# SOC_DDR.net
KiCad netlist of a schematic drawn in Altium Designer
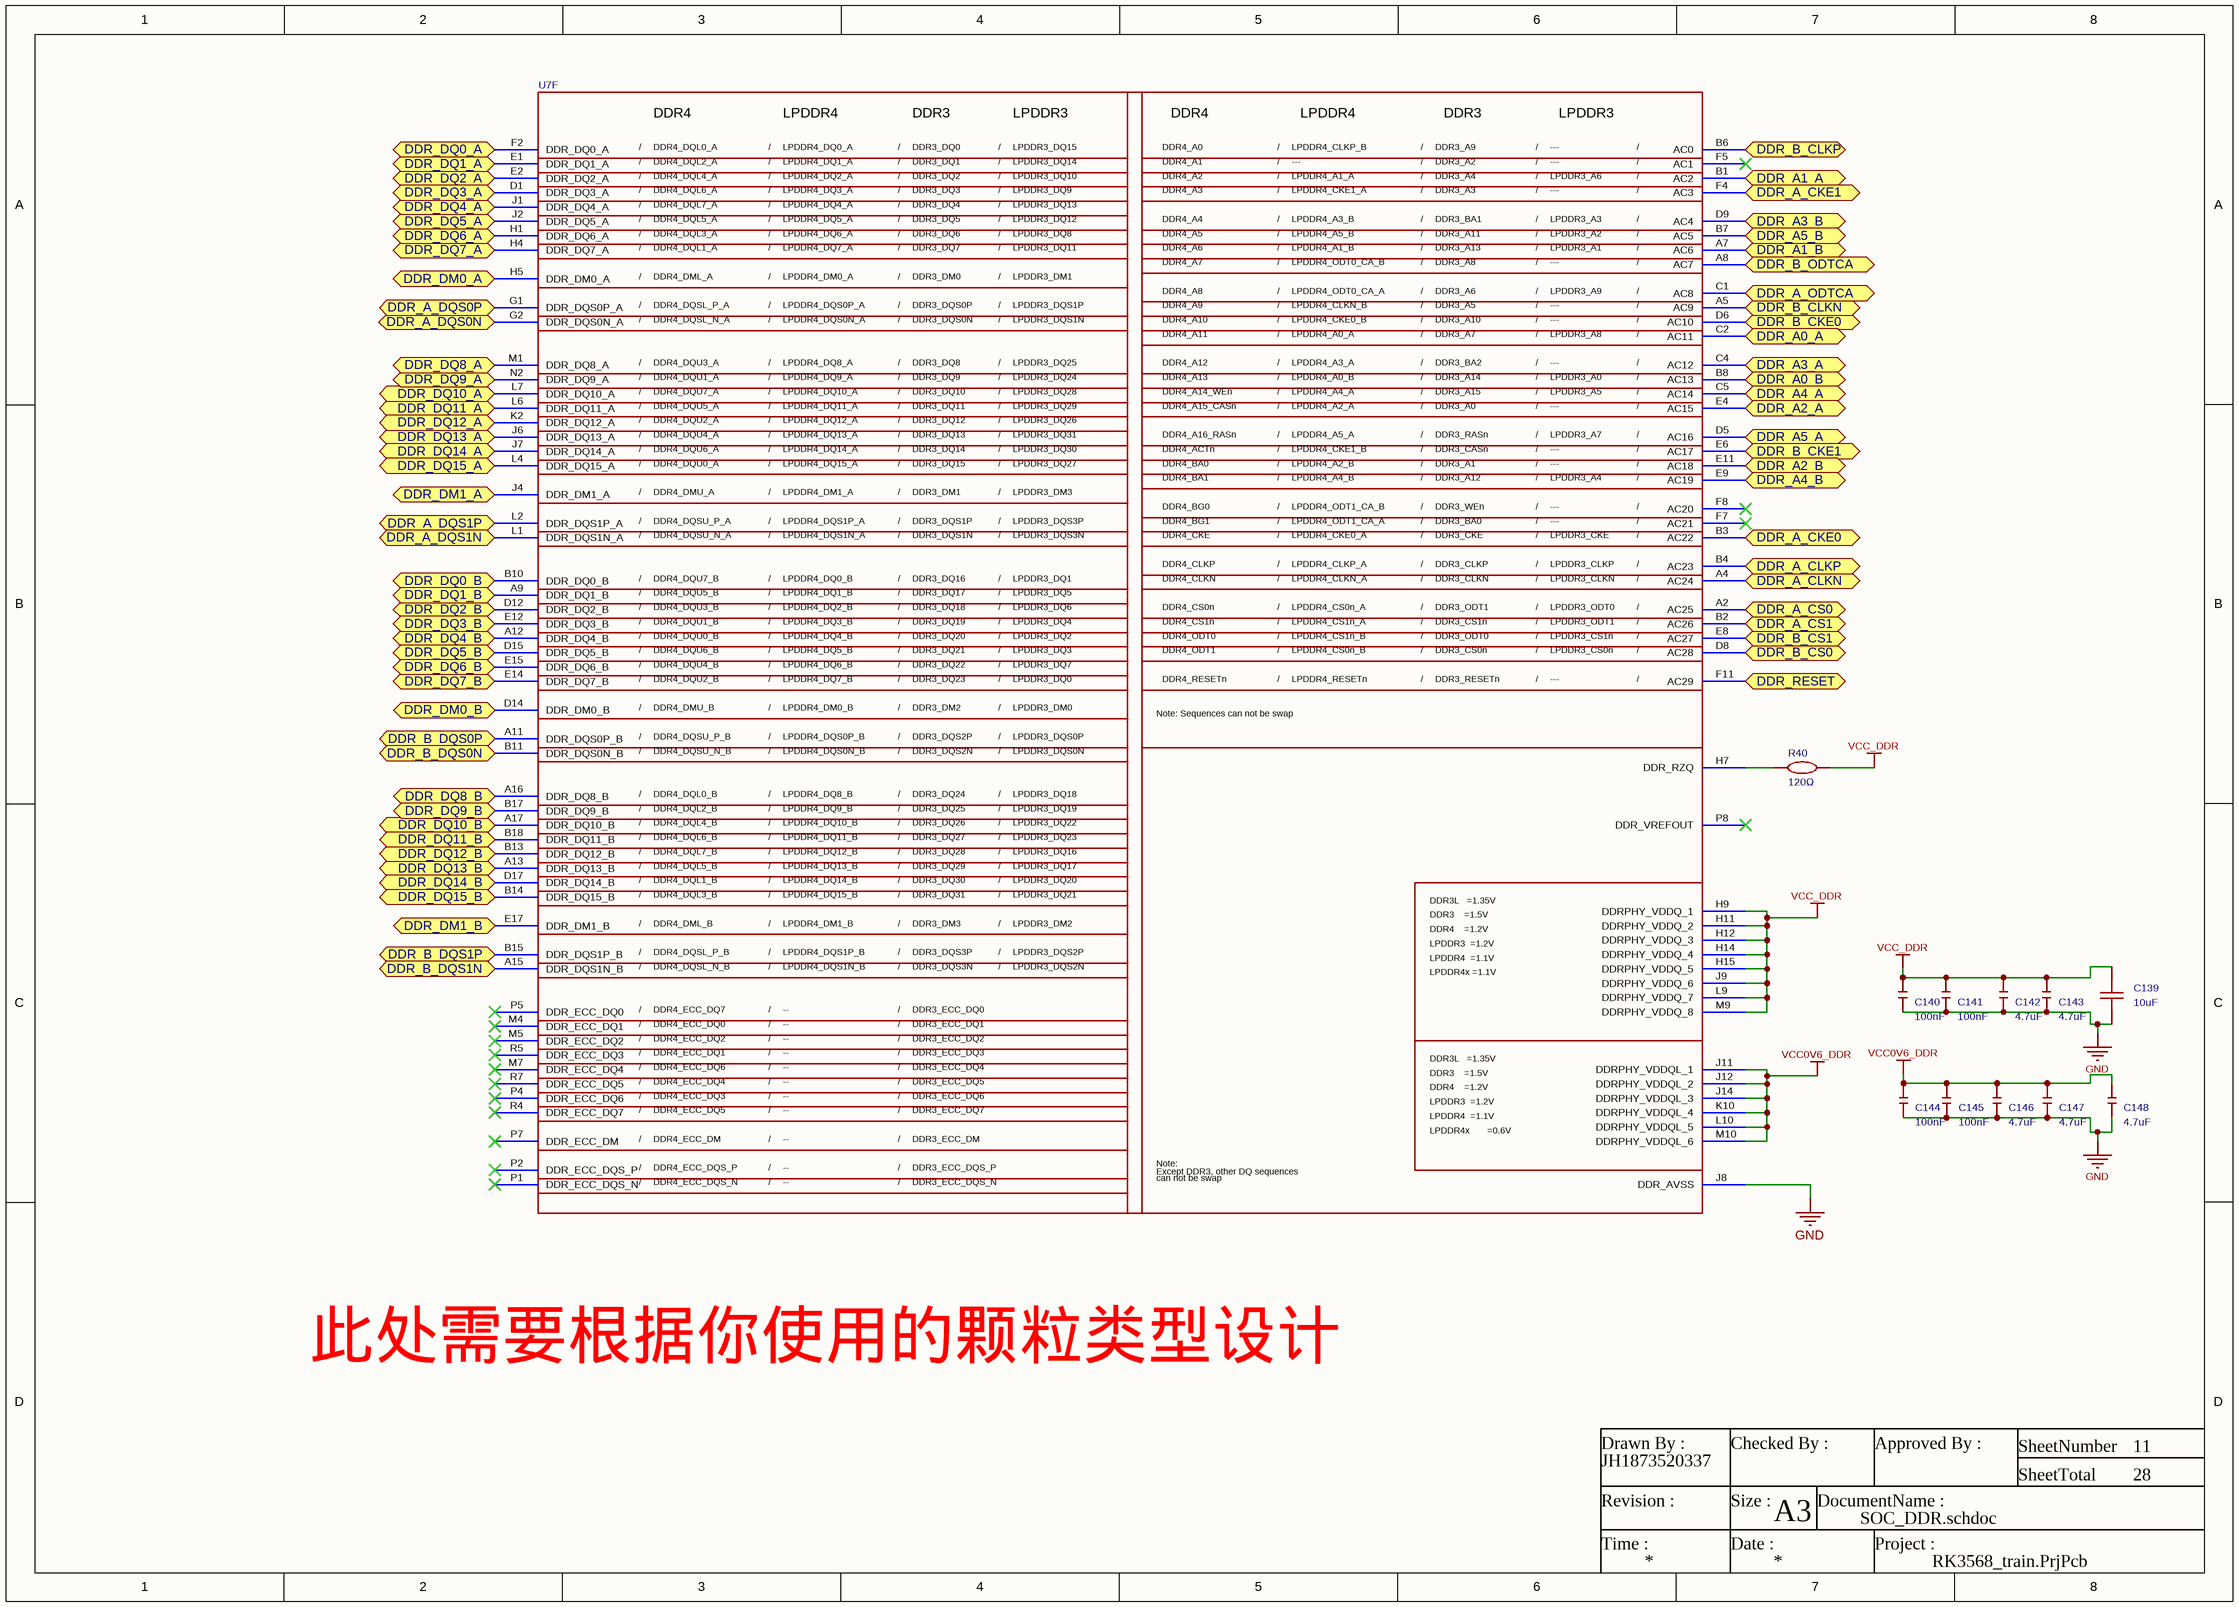
[diagram p0: SOC_DDR.schdoc]

(export (version "E")
  (design (tool "Eeschema 10.0.6"))
  (components
    (comp (ref "C139")
      (value "10uF")
      (footprint "C0603")
      (libsource (lib "altium-import") (part "root_1_CAP_0603_"))
    )
    (comp (ref "C140")
      (value "100nF")
      (footprint "MYC0201")
      (description "my0201")
      (libsource (lib "altium-import") (part "root_1_MY_C0201_"))
    )
    (comp (ref "C141")
      (value "100nF")
      (footprint "MYC0201")
      (description "my0201")
      (libsource (lib "altium-import") (part "root_1_MY_C0201_"))
    )
    (comp (ref "C142")
      (value "4.7uF")
      (footprint "MYC0402")
      (description "C0402电容")
      (libsource (lib "altium-import") (part "root_1_MYC0402_"))
    )
    (comp (ref "C143")
      (value "4.7uF")
      (footprint "MYC0402")
      (description "C0402电容")
      (libsource (lib "altium-import") (part "root_1_MYC0402_"))
    )
    (comp (ref "C144")
      (value "100nF")
      (footprint "MYC0201")
      (description "my0201")
      (libsource (lib "altium-import") (part "root_1_MY_C0201_"))
    )
    (comp (ref "C145")
      (value "100nF")
      (footprint "MYC0201")
      (description "my0201")
      (libsource (lib "altium-import") (part "root_1_MY_C0201_"))
    )
    (comp (ref "C146")
      (value "4.7uF")
      (footprint "MYC0402")
      (description "C0402电容")
      (libsource (lib "altium-import") (part "root_1_MYC0402_"))
    )
    (comp (ref "C147")
      (value "4.7uF")
      (footprint "MYC0402")
      (description "C0402电容")
      (libsource (lib "altium-import") (part "root_1_MYC0402_"))
    )
    (comp (ref "C148")
      (value "4.7uF")
      (footprint "MYC0402")
      (description "C0402电容")
      (libsource (lib "altium-import") (part "root_1_MYC0402_"))
    )
    (comp (ref "R40")
      (value "120Ω")
      (footprint "R0201")
      (libsource (lib "altium-import") (part "root_0_Res_0201_"))
    )
    (comp (ref "U7")
      (value "RK3568")
      (footprint "BGA-636_L19.0-W19.0-P0.65-BL")
      (libsource (lib "altium-import") (part "root_0_RK3568_"))
    )
  )
  (nets
    (net (code "1") (name "/DDR_A0_A") (class "Default")
      (node (ref "U7") (pin "C2") (pinfunction "AC11_C2") (pintype "passive"))
    )
    (net (code "2") (name "/DDR_A0_B") (class "Default")
      (node (ref "U7") (pin "B8") (pinfunction "AC13_B8") (pintype "passive"))
    )
    (net (code "3") (name "/DDR_A1_A") (class "Default")
      (node (ref "U7") (pin "B1") (pinfunction "AC2_B1") (pintype "passive"))
    )
    (net (code "4") (name "/DDR_A1_B") (class "Default")
      (node (ref "U7") (pin "A7") (pinfunction "AC6_A7") (pintype "passive"))
    )
    (net (code "5") (name "/DDR_A2_A") (class "Default")
      (node (ref "U7") (pin "E4") (pinfunction "AC15_E4") (pintype "passive"))
    )
    (net (code "6") (name "/DDR_A2_B") (class "Default")
      (node (ref "U7") (pin "E11") (pinfunction "AC18_E11") (pintype "passive"))
    )
    (net (code "7") (name "/DDR_A3_A") (class "Default")
      (node (ref "U7") (pin "C4") (pinfunction "AC12_C4") (pintype "passive"))
    )
    (net (code "8") (name "/DDR_A3_B") (class "Default")
      (node (ref "U7") (pin "D9") (pinfunction "AC4_D9") (pintype "passive"))
    )
    (net (code "9") (name "/DDR_A4_A") (class "Default")
      (node (ref "U7") (pin "C5") (pinfunction "AC14_C5") (pintype "passive"))
    )
    (net (code "10") (name "/DDR_A4_B") (class "Default")
      (node (ref "U7") (pin "E9") (pinfunction "AC19_E9") (pintype "passive"))
    )
    (net (code "11") (name "/DDR_A5_A") (class "Default")
      (node (ref "U7") (pin "D5") (pinfunction "AC16_D5") (pintype "passive"))
    )
    (net (code "12") (name "/DDR_A5_B") (class "Default")
      (node (ref "U7") (pin "B7") (pinfunction "AC5_B7") (pintype "passive"))
    )
    (net (code "13") (name "/DDR_A_CKE0") (class "Default")
      (node (ref "U7") (pin "B3") (pinfunction "AC22_B3") (pintype "passive"))
    )
    (net (code "14") (name "/DDR_A_CKE1") (class "Default")
      (node (ref "U7") (pin "F4") (pinfunction "AC3_F4") (pintype "passive"))
    )
    (net (code "15") (name "/DDR_A_CLKN") (class "Default")
      (node (ref "U7") (pin "A4") (pinfunction "AC24_A4") (pintype "passive"))
    )
    (net (code "16") (name "/DDR_A_CLKP") (class "Default")
      (node (ref "U7") (pin "B4") (pinfunction "AC23_B4") (pintype "passive"))
    )
    (net (code "17") (name "/DDR_A_CS0") (class "Default")
      (node (ref "U7") (pin "A2") (pinfunction "AC25_A2") (pintype "passive"))
    )
    (net (code "18") (name "/DDR_A_CS1") (class "Default")
      (node (ref "U7") (pin "B2") (pinfunction "AC26_B2") (pintype "passive"))
    )
    (net (code "19") (name "/DDR_A_DQS0N") (class "Default")
      (node (ref "U7") (pin "G2") (pinfunction "DDR_DQS0N_A_G2") (pintype "passive"))
    )
    (net (code "20") (name "/DDR_A_DQS0P") (class "Default")
      (node (ref "U7") (pin "G1") (pinfunction "DDR_DQS0P_A_G1") (pintype "passive"))
    )
    (net (code "21") (name "/DDR_A_DQS1N") (class "Default")
      (node (ref "U7") (pin "L1") (pinfunction "DDR_DQS1N_A_L1") (pintype "passive"))
    )
    (net (code "22") (name "/DDR_A_DQS1P") (class "Default")
      (node (ref "U7") (pin "L2") (pinfunction "DDR_DQS1P_A_L2") (pintype "passive"))
    )
    (net (code "23") (name "/DDR_A_ODTCA") (class "Default")
      (node (ref "U7") (pin "C1") (pinfunction "AC8_C1") (pintype "passive"))
    )
    (net (code "24") (name "/DDR_B_CKE0") (class "Default")
      (node (ref "U7") (pin "D6") (pinfunction "AC10_D6") (pintype "passive"))
    )
    (net (code "25") (name "/DDR_B_CKE1") (class "Default")
      (node (ref "U7") (pin "E6") (pinfunction "AC17_E6") (pintype "passive"))
    )
    (net (code "26") (name "/DDR_B_CLKN") (class "Default")
      (node (ref "U7") (pin "A5") (pinfunction "AC9_A5") (pintype "passive"))
    )
    (net (code "27") (name "/DDR_B_CLKP") (class "Default")
      (node (ref "U7") (pin "B6") (pinfunction "AC0_B6") (pintype "passive"))
    )
    (net (code "28") (name "/DDR_B_CS0") (class "Default")
      (node (ref "U7") (pin "D8") (pinfunction "AC28_D8") (pintype "passive"))
    )
    (net (code "29") (name "/DDR_B_CS1") (class "Default")
      (node (ref "U7") (pin "E8") (pinfunction "AC27_E8") (pintype "passive"))
    )
    (net (code "30") (name "/DDR_B_DQS0N") (class "Default")
      (node (ref "U7") (pin "B11") (pinfunction "DDR_DQS0N_B_B11") (pintype "passive"))
    )
    (net (code "31") (name "/DDR_B_DQS0P") (class "Default")
      (node (ref "U7") (pin "A11") (pinfunction "DDR_DQS0P_B_A11") (pintype "passive"))
    )
    (net (code "32") (name "/DDR_B_DQS1N") (class "Default")
      (node (ref "U7") (pin "A15") (pinfunction "DDR_DQS1N_B_A15") (pintype "passive"))
    )
    (net (code "33") (name "/DDR_B_DQS1P") (class "Default")
      (node (ref "U7") (pin "B15") (pinfunction "DDR_DQS1P_B_B15") (pintype "passive"))
    )
    (net (code "34") (name "/DDR_B_ODTCA") (class "Default")
      (node (ref "U7") (pin "A8") (pinfunction "AC7_A8") (pintype "passive"))
    )
    (net (code "35") (name "/DDR_DM0_A") (class "Default")
      (node (ref "U7") (pin "H5") (pinfunction "DDR_DM0_A_H5") (pintype "passive"))
    )
    (net (code "36") (name "/DDR_DM0_B") (class "Default")
      (node (ref "U7") (pin "D14") (pinfunction "DDR_DM0_B_D14") (pintype "passive"))
    )
    (net (code "37") (name "/DDR_DM1_A") (class "Default")
      (node (ref "U7") (pin "J4") (pinfunction "DDR_DM1_A_J4") (pintype "passive"))
    )
    (net (code "38") (name "/DDR_DM1_B") (class "Default")
      (node (ref "U7") (pin "E17") (pinfunction "DDR_DM1_B_E17") (pintype "passive"))
    )
    (net (code "39") (name "/DDR_DQ0_A") (class "Default")
      (node (ref "U7") (pin "F2") (pinfunction "DDR_DQ0_A_F2") (pintype "passive"))
    )
    (net (code "40") (name "/DDR_DQ0_B") (class "Default")
      (node (ref "U7") (pin "B10") (pinfunction "DDR_DQ0_B_B10") (pintype "passive"))
    )
    (net (code "41") (name "/DDR_DQ1_A") (class "Default")
      (node (ref "U7") (pin "E1") (pinfunction "DDR_DQ1_A_E1") (pintype "passive"))
    )
    (net (code "42") (name "/DDR_DQ1_B") (class "Default")
      (node (ref "U7") (pin "A9") (pinfunction "DDR_DQ1_B_A9") (pintype "passive"))
    )
    (net (code "43") (name "/DDR_DQ2_A") (class "Default")
      (node (ref "U7") (pin "E2") (pinfunction "DDR_DQ2_A_E2") (pintype "passive"))
    )
    (net (code "44") (name "/DDR_DQ2_B") (class "Default")
      (node (ref "U7") (pin "D12") (pinfunction "DDR_DQ2_B_D12") (pintype "passive"))
    )
    (net (code "45") (name "/DDR_DQ3_A") (class "Default")
      (node (ref "U7") (pin "D1") (pinfunction "DDR_DQ3_A_D1") (pintype "passive"))
    )
    (net (code "46") (name "/DDR_DQ3_B") (class "Default")
      (node (ref "U7") (pin "E12") (pinfunction "DDR_DQ3_B_E12") (pintype "passive"))
    )
    (net (code "47") (name "/DDR_DQ4_A") (class "Default")
      (node (ref "U7") (pin "J1") (pinfunction "DDR_DQ4_A_J1") (pintype "passive"))
    )
    (net (code "48") (name "/DDR_DQ4_B") (class "Default")
      (node (ref "U7") (pin "A12") (pinfunction "DDR_DQ4_B_A12") (pintype "passive"))
    )
    (net (code "49") (name "/DDR_DQ5_A") (class "Default")
      (node (ref "U7") (pin "J2") (pinfunction "DDR_DQ5_A_J2") (pintype "passive"))
    )
    (net (code "50") (name "/DDR_DQ5_B") (class "Default")
      (node (ref "U7") (pin "D15") (pinfunction "DDR_DQ5_B_D15") (pintype "passive"))
    )
    (net (code "51") (name "/DDR_DQ6_A") (class "Default")
      (node (ref "U7") (pin "H1") (pinfunction "DDR_DQ6_A_H1") (pintype "passive"))
    )
    (net (code "52") (name "/DDR_DQ6_B") (class "Default")
      (node (ref "U7") (pin "E15") (pinfunction "DDR_DQ6_B_E15") (pintype "passive"))
    )
    (net (code "53") (name "/DDR_DQ7_A") (class "Default")
      (node (ref "U7") (pin "H4") (pinfunction "DDR_DQ7_A_H4") (pintype "passive"))
    )
    (net (code "54") (name "/DDR_DQ7_B") (class "Default")
      (node (ref "U7") (pin "E14") (pinfunction "DDR_DQ7_B_E14") (pintype "passive"))
    )
    (net (code "55") (name "/DDR_DQ8_A") (class "Default")
      (node (ref "U7") (pin "M1") (pinfunction "DDR_DQ8_A_M1") (pintype "passive"))
    )
    (net (code "56") (name "/DDR_DQ8_B") (class "Default")
      (node (ref "U7") (pin "A16") (pinfunction "DDR_DQ8_B_A16") (pintype "passive"))
    )
    (net (code "57") (name "/DDR_DQ9_A") (class "Default")
      (node (ref "U7") (pin "N2") (pinfunction "DDR_DQ9_A_N2") (pintype "passive"))
    )
    (net (code "58") (name "/DDR_DQ9_B") (class "Default")
      (node (ref "U7") (pin "B17") (pinfunction "DDR_DQ9_B_B17") (pintype "passive"))
    )
    (net (code "59") (name "/DDR_DQ10_A") (class "Default")
      (node (ref "U7") (pin "L7") (pinfunction "DDR_DQ10_A_L7") (pintype "passive"))
    )
    (net (code "60") (name "/DDR_DQ10_B") (class "Default")
      (node (ref "U7") (pin "A17") (pinfunction "DDR_DQ10_B_A17") (pintype "passive"))
    )
    (net (code "61") (name "/DDR_DQ11_A") (class "Default")
      (node (ref "U7") (pin "L6") (pinfunction "DDR_DQ11_A_L6") (pintype "passive"))
    )
    (net (code "62") (name "/DDR_DQ11_B") (class "Default")
      (node (ref "U7") (pin "B18") (pinfunction "DDR_DQ11_B_B18") (pintype "passive"))
    )
    (net (code "63") (name "/DDR_DQ12_A") (class "Default")
      (node (ref "U7") (pin "K2") (pinfunction "DDR_DQ12_A_K2") (pintype "passive"))
    )
    (net (code "64") (name "/DDR_DQ12_B") (class "Default")
      (node (ref "U7") (pin "B13") (pinfunction "DDR_DQ12_B_B13") (pintype "passive"))
    )
    (net (code "65") (name "/DDR_DQ13_A") (class "Default")
      (node (ref "U7") (pin "J6") (pinfunction "DDR_DQ13_A_J6") (pintype "passive"))
    )
    (net (code "66") (name "/DDR_DQ13_B") (class "Default")
      (node (ref "U7") (pin "A13") (pinfunction "DDR_DQ13_B_A13") (pintype "passive"))
    )
    (net (code "67") (name "/DDR_DQ14_A") (class "Default")
      (node (ref "U7") (pin "J7") (pinfunction "DDR_DQ14_A_J7") (pintype "passive"))
    )
    (net (code "68") (name "/DDR_DQ14_B") (class "Default")
      (node (ref "U7") (pin "D17") (pinfunction "DDR_DQ14_B_D17") (pintype "passive"))
    )
    (net (code "69") (name "/DDR_DQ15_A") (class "Default")
      (node (ref "U7") (pin "L4") (pinfunction "DDR_DQ15_A_L4") (pintype "passive"))
    )
    (net (code "70") (name "/DDR_DQ15_B") (class "Default")
      (node (ref "U7") (pin "B14") (pinfunction "DDR_DQ15_B_B14") (pintype "passive"))
    )
    (net (code "71") (name "/DDR_RESET") (class "Default")
      (node (ref "U7") (pin "F11") (pinfunction "AC29_F11") (pintype "passive"))
    )
    (net (code "72") (name "GND") (class "Default")
      (node (ref "C139") (pin "1") (pinfunction "1_1") (pintype "passive"))
      (node (ref "C140") (pin "1") (pinfunction "1_1") (pintype "passive"))
      (node (ref "C141") (pin "1") (pinfunction "1_1") (pintype "passive"))
      (node (ref "C142") (pin "1") (pinfunction "1_1") (pintype "passive"))
      (node (ref "C143") (pin "1") (pinfunction "1_1") (pintype "passive"))
      (node (ref "C144") (pin "1") (pinfunction "1_1") (pintype "passive"))
      (node (ref "C145") (pin "1") (pinfunction "1_1") (pintype "passive"))
      (node (ref "C146") (pin "1") (pinfunction "1_1") (pintype "passive"))
      (node (ref "C147") (pin "1") (pinfunction "1_1") (pintype "passive"))
      (node (ref "C148") (pin "1") (pinfunction "1_1") (pintype "passive"))
      (node (ref "U7") (pin "J8") (pinfunction "DDR_AVSS_J8") (pintype "passive"))
    )
    (net (code "73") (name "Net-(U7F-DDR_RZQ)") (class "Default")
      (node (ref "R40") (pin "1") (pinfunction "1_1") (pintype "passive"))
      (node (ref "U7") (pin "H7") (pinfunction "DDR_RZQ_H7") (pintype "passive"))
    )
    (net (code "74") (name "VCC0V6_DDR") (class "Default")
      (node (ref "C144") (pin "2") (pinfunction "2_2") (pintype "passive"))
      (node (ref "C145") (pin "2") (pinfunction "2_2") (pintype "passive"))
      (node (ref "C146") (pin "2") (pinfunction "2_2") (pintype "passive"))
      (node (ref "C147") (pin "2") (pinfunction "2_2") (pintype "passive"))
      (node (ref "C148") (pin "2") (pinfunction "2_2") (pintype "passive"))
      (node (ref "U7") (pin "J11") (pinfunction "DDRPHY_VDDQL_1_J11") (pintype "passive"))
      (node (ref "U7") (pin "J12") (pinfunction "DDRPHY_VDDQL_2_J12") (pintype "passive"))
      (node (ref "U7") (pin "J14") (pinfunction "DDRPHY_VDDQL_3_J14") (pintype "passive"))
      (node (ref "U7") (pin "K10") (pinfunction "DDRPHY_VDDQL_4_K10") (pintype "passive"))
      (node (ref "U7") (pin "L10") (pinfunction "DDRPHY_VDDQL_5_L10") (pintype "passive"))
      (node (ref "U7") (pin "M10") (pinfunction "DDRPHY_VDDQL_6_M10") (pintype "passive"))
    )
    (net (code "75") (name "VCC_DDR") (class "Default")
      (node (ref "C139") (pin "2") (pinfunction "2_2") (pintype "passive"))
      (node (ref "C140") (pin "2") (pinfunction "2_2") (pintype "passive"))
      (node (ref "C141") (pin "2") (pinfunction "2_2") (pintype "passive"))
      (node (ref "C142") (pin "2") (pinfunction "2_2") (pintype "passive"))
      (node (ref "C143") (pin "2") (pinfunction "2_2") (pintype "passive"))
      (node (ref "R40") (pin "2") (pinfunction "2_2") (pintype "passive"))
      (node (ref "U7") (pin "H11") (pinfunction "DDRPHY_VDDQ_2_H11") (pintype "passive"))
      (node (ref "U7") (pin "H12") (pinfunction "DDRPHY_VDDQ_3_H12") (pintype "passive"))
      (node (ref "U7") (pin "H14") (pinfunction "DDRPHY_VDDQ_4_H14") (pintype "passive"))
      (node (ref "U7") (pin "H15") (pinfunction "DDRPHY_VDDQ_5_H15") (pintype "passive"))
      (node (ref "U7") (pin "H9") (pinfunction "DDRPHY_VDDQ_1_H9") (pintype "passive"))
      (node (ref "U7") (pin "J9") (pinfunction "DDRPHY_VDDQ_6_J9") (pintype "passive"))
      (node (ref "U7") (pin "L9") (pinfunction "DDRPHY_VDDQ_7_L9") (pintype "passive"))
      (node (ref "U7") (pin "M9") (pinfunction "DDRPHY_VDDQ_8_M9") (pintype "passive"))
    )
    (net (code "76") (name "unconnected-(U7F-AC1-PadF5)") (class "Default")
      (node (ref "U7") (pin "F5") (pinfunction "AC1_F5") (pintype "passive+no_connect"))
    )
    (net (code "77") (name "unconnected-(U7F-AC20-PadF8)") (class "Default")
      (node (ref "U7") (pin "F8") (pinfunction "AC20_F8") (pintype "passive+no_connect"))
    )
    (net (code "78") (name "unconnected-(U7F-AC21-PadF7)") (class "Default")
      (node (ref "U7") (pin "F7") (pinfunction "AC21_F7") (pintype "passive+no_connect"))
    )
    (net (code "79") (name "unconnected-(U7F-DDR_ECC_DM-PadP7)") (class "Default")
      (node (ref "U7") (pin "P7") (pinfunction "DDR_ECC_DM_P7") (pintype "passive+no_connect"))
    )
    (net (code "80") (name "unconnected-(U7F-DDR_ECC_DQ0-PadP5)") (class "Default")
      (node (ref "U7") (pin "P5") (pinfunction "DDR_ECC_DQ0_P5") (pintype "passive+no_connect"))
    )
    (net (code "81") (name "unconnected-(U7F-DDR_ECC_DQ1-PadM4)") (class "Default")
      (node (ref "U7") (pin "M4") (pinfunction "DDR_ECC_DQ1_M4") (pintype "passive+no_connect"))
    )
    (net (code "82") (name "unconnected-(U7F-DDR_ECC_DQ2-PadM5)") (class "Default")
      (node (ref "U7") (pin "M5") (pinfunction "DDR_ECC_DQ2_M5") (pintype "passive+no_connect"))
    )
    (net (code "83") (name "unconnected-(U7F-DDR_ECC_DQ3-PadR5)") (class "Default")
      (node (ref "U7") (pin "R5") (pinfunction "DDR_ECC_DQ3_R5") (pintype "passive+no_connect"))
    )
    (net (code "84") (name "unconnected-(U7F-DDR_ECC_DQ4-PadM7)") (class "Default")
      (node (ref "U7") (pin "M7") (pinfunction "DDR_ECC_DQ4_M7") (pintype "passive+no_connect"))
    )
    (net (code "85") (name "unconnected-(U7F-DDR_ECC_DQ5-PadR7)") (class "Default")
      (node (ref "U7") (pin "R7") (pinfunction "DDR_ECC_DQ5_R7") (pintype "passive+no_connect"))
    )
    (net (code "86") (name "unconnected-(U7F-DDR_ECC_DQ6-PadP4)") (class "Default")
      (node (ref "U7") (pin "P4") (pinfunction "DDR_ECC_DQ6_P4") (pintype "passive+no_connect"))
    )
    (net (code "87") (name "unconnected-(U7F-DDR_ECC_DQ7-PadR4)") (class "Default")
      (node (ref "U7") (pin "R4") (pinfunction "DDR_ECC_DQ7_R4") (pintype "passive+no_connect"))
    )
    (net (code "88") (name "unconnected-(U7F-DDR_ECC_DQS_N-PadP1)") (class "Default")
      (node (ref "U7") (pin "P1") (pinfunction "DDR_ECC_DQS_N_P1") (pintype "passive+no_connect"))
    )
    (net (code "89") (name "unconnected-(U7F-DDR_ECC_DQS_P-PadP2)") (class "Default")
      (node (ref "U7") (pin "P2") (pinfunction "DDR_ECC_DQS_P_P2") (pintype "passive+no_connect"))
    )
    (net (code "90") (name "unconnected-(U7F-DDR_VREFOUT-PadP8)") (class "Default")
      (node (ref "U7") (pin "P8") (pinfunction "DDR_VREFOUT_P8") (pintype "passive+no_connect"))
    )
  )
)
